# Microcontroleur.net
KiCad netlist of a schematic drawn in Altium Designer
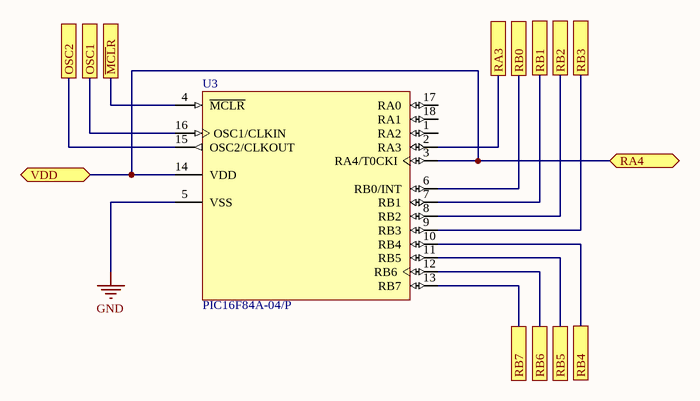
[diagram p0: Microcontroleur.SchDoc]

(export (version "E")
  (design (tool "Eeschema 10.0.6"))
  (components
    (comp (ref "U3")
      (value "PIC16F84A-04/P")
      (footprint "PDIP300-P18")
      (fields (field (name "PUBLISHER") "Altium Limited"))
      (libsource (lib "Microchip Microcontroller 8-Bit PIC16") (part "PIC16F84A-04/P"))
    )
  )
  (nets
    (net (code "1") (name "/OSC1") (class "Default")
      (node (ref "U3") (pin "16") (pinfunction "OSC1/CLKIN_16") (pintype "input"))
    )
    (net (code "2") (name "/OSC2") (class "Default")
      (node (ref "U3") (pin "15") (pinfunction "OSC2/CLKOUT_15") (pintype "output"))
    )
    (net (code "3") (name "/RA3") (class "Default")
      (node (ref "U3") (pin "2") (pinfunction "RA3_2") (pintype "bidirectional"))
    )
    (net (code "4") (name "/RA4") (class "Default")
      (node (ref "U3") (pin "14") (pinfunction "VDD_14") (pintype "power_in"))
      (node (ref "U3") (pin "3") (pinfunction "RA4/T0CKI_3") (pintype "bidirectional"))
    )
    (net (code "5") (name "/RB0") (class "Default")
      (node (ref "U3") (pin "6") (pinfunction "RB0/INT_6") (pintype "bidirectional"))
    )
    (net (code "6") (name "/RB1") (class "Default")
      (node (ref "U3") (pin "7") (pinfunction "RB1_7") (pintype "bidirectional"))
    )
    (net (code "7") (name "/RB2") (class "Default")
      (node (ref "U3") (pin "8") (pinfunction "RB2_8") (pintype "bidirectional"))
    )
    (net (code "8") (name "/RB3") (class "Default")
      (node (ref "U3") (pin "9") (pinfunction "RB3_9") (pintype "bidirectional"))
    )
    (net (code "9") (name "/RB4") (class "Default")
      (node (ref "U3") (pin "10") (pinfunction "RB4_10") (pintype "bidirectional"))
    )
    (net (code "10") (name "/RB5") (class "Default")
      (node (ref "U3") (pin "11") (pinfunction "RB5_11") (pintype "bidirectional"))
    )
    (net (code "11") (name "/RB6") (class "Default")
      (node (ref "U3") (pin "12") (pinfunction "RB6_12") (pintype "bidirectional"))
    )
    (net (code "12") (name "/RB7") (class "Default")
      (node (ref "U3") (pin "13") (pinfunction "RB7_13") (pintype "bidirectional"))
    )
    (net (code "13") (name "/~{MCL}R") (class "Default")
      (node (ref "U3") (pin "4") (pinfunction "~{MCLR}_4") (pintype "input"))
    )
    (net (code "14") (name "GND") (class "Default")
      (node (ref "U3") (pin "5") (pinfunction "VSS_5") (pintype "power_in"))
    )
    (net (code "15") (name "unconnected-(U3-RA0-Pad17)") (class "Default")
      (node (ref "U3") (pin "17") (pinfunction "RA0_17") (pintype "bidirectional"))
    )
    (net (code "16") (name "unconnected-(U3-RA1-Pad18)") (class "Default")
      (node (ref "U3") (pin "18") (pinfunction "RA1_18") (pintype "bidirectional"))
    )
    (net (code "17") (name "unconnected-(U3-RA2-Pad1)") (class "Default")
      (node (ref "U3") (pin "1") (pinfunction "RA2_1") (pintype "bidirectional"))
    )
  )
)
